# CORE.net
KiCad netlist of a schematic drawn in Altium Designer
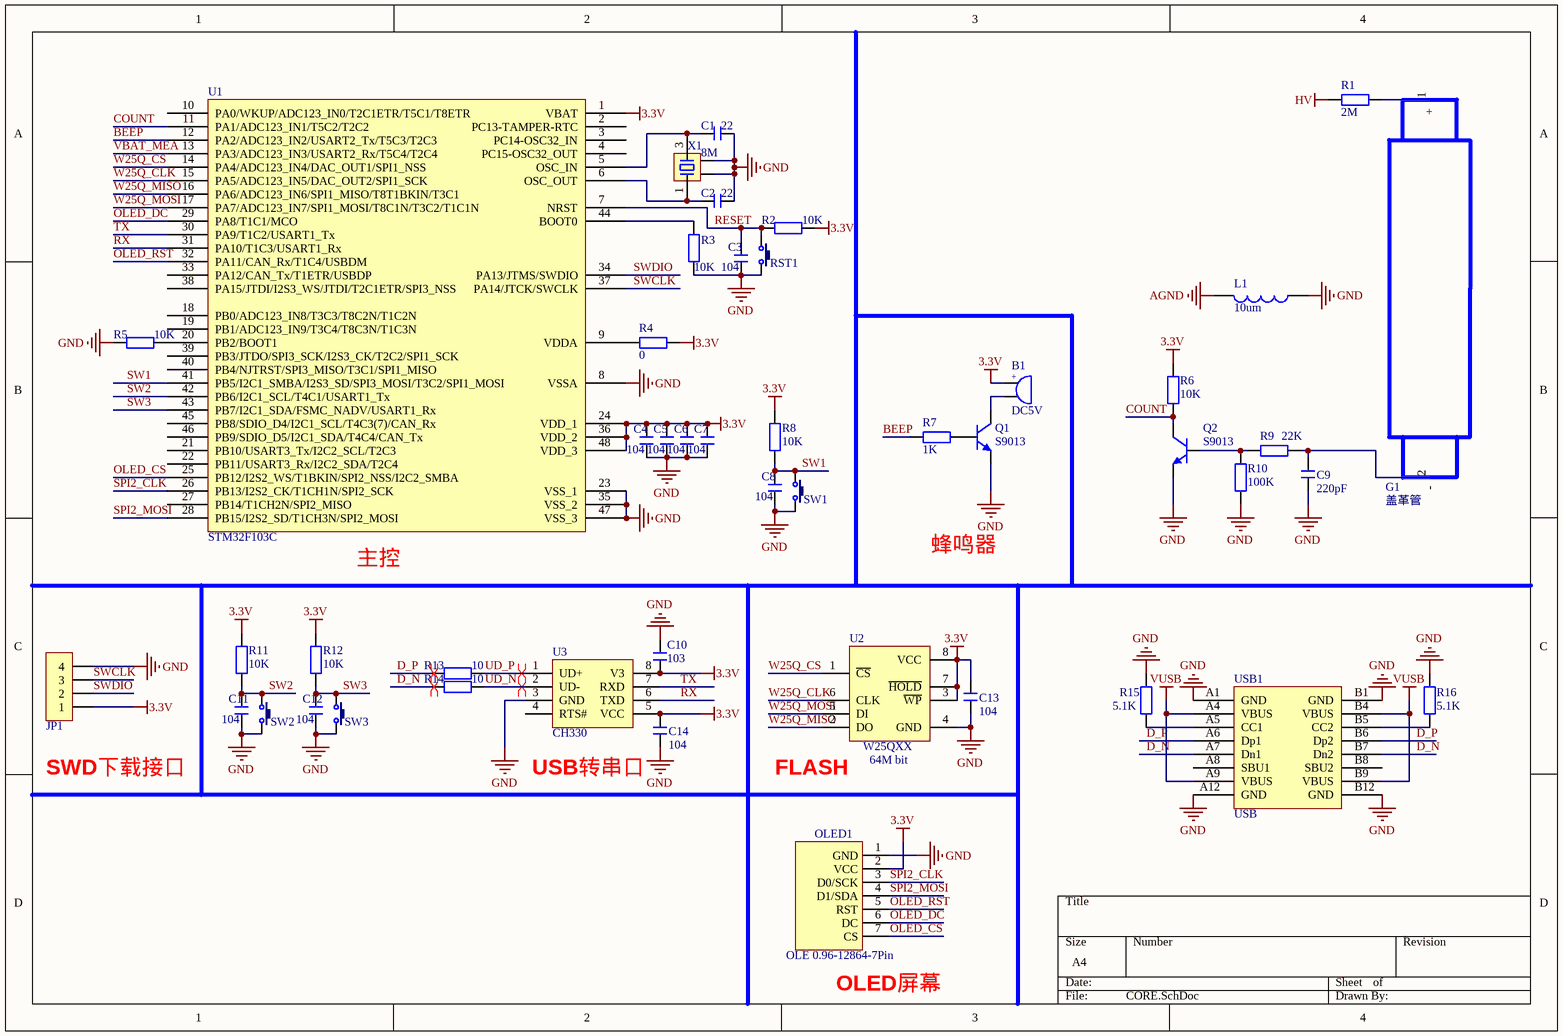
[diagram p0: CORE.SchDoc]

(export (version "E")
  (design (tool "Eeschema 10.0.6"))
  (components
    (comp (ref "B1")
      (value "DC5V")
      (footprint "BEEP 5x9x5.5")
      (description "蜂鸣器")
      (fields (field (name "版权归属") "源创客"))
      (libsource (lib "未分类器件") (part "BEEP"))
    )
    (comp (ref "C1")
      (value "22")
      (footprint "C 0603")
      (description "无极性贴片电容")
      (fields (field (name "版权归属") "源创客"))
      (libsource (lib "电阻-电容-电感") (part "C"))
    )
    (comp (ref "C2")
      (value "22")
      (footprint "C 0603")
      (description "无极性贴片电容")
      (fields (field (name "版权归属") "源创客"))
      (libsource (lib "电阻-电容-电感") (part "C"))
    )
    (comp (ref "C3")
      (value "104")
      (footprint "C 0603")
      (description "无极性贴片电容")
      (fields (field (name "版权归属") "源创客"))
      (libsource (lib "电阻-电容-电感") (part "C"))
    )
    (comp (ref "C4")
      (value "104")
      (footprint "C 0603")
      (description "无极性贴片电容")
      (fields (field (name "版权归属") "源创客"))
      (libsource (lib "电阻-电容-电感") (part "C"))
    )
    (comp (ref "C5")
      (value "104")
      (footprint "C 0603")
      (description "无极性贴片电容")
      (fields (field (name "版权归属") "源创客"))
      (libsource (lib "电阻-电容-电感") (part "C"))
    )
    (comp (ref "C6")
      (value "104")
      (footprint "C 0603")
      (description "无极性贴片电容")
      (fields (field (name "版权归属") "源创客"))
      (libsource (lib "电阻-电容-电感") (part "C"))
    )
    (comp (ref "C7")
      (value "104")
      (footprint "C 0603")
      (description "无极性贴片电容")
      (fields (field (name "版权归属") "源创客"))
      (libsource (lib "电阻-电容-电感") (part "C"))
    )
    (comp (ref "C8")
      (value "104")
      (footprint "C 0603")
      (description "无极性贴片电容")
      (fields (field (name "版权归属") "源创客"))
      (libsource (lib "电阻-电容-电感") (part "C"))
    )
    (comp (ref "C9")
      (value "220pF")
      (footprint "C 0603")
      (description "无极性贴片电容")
      (fields (field (name "版权归属") "源创客"))
      (libsource (lib "电阻-电容-电感") (part "C"))
    )
    (comp (ref "C10")
      (value "103")
      (footprint "C 0603")
      (description "无极性贴片电容")
      (fields (field (name "版权归属") "源创客"))
      (libsource (lib "电阻-电容-电感") (part "C"))
    )
    (comp (ref "C11")
      (value "104")
      (footprint "C 0603")
      (description "无极性贴片电容")
      (fields (field (name "版权归属") "源创客"))
      (libsource (lib "电阻-电容-电感") (part "C"))
    )
    (comp (ref "C12")
      (value "104")
      (footprint "C 0603")
      (description "无极性贴片电容")
      (fields (field (name "版权归属") "源创客"))
      (libsource (lib "电阻-电容-电感") (part "C"))
    )
    (comp (ref "C13")
      (value "104")
      (footprint "C 0603")
      (description "无极性贴片电容")
      (fields (field (name "版权归属") "源创客"))
      (libsource (lib "电阻-电容-电感") (part "C"))
    )
    (comp (ref "C14")
      (value "104")
      (footprint "C 0603")
      (description "无极性贴片电容")
      (fields (field (name "版权归属") "源创客"))
      (libsource (lib "电阻-电容-电感") (part "C"))
    )
    (comp (ref "G1")
      (value "盖革管")
      (footprint "SI3BG 2")
      (description "小型高量程SI3BG GM管")
      (libsource (lib "MYLIB") (part "盖革管"))
    )
    (comp (ref "JP1")
      (value "HDR-1X4")
      (footprint "SH1.0-4P-L")
      (description "4P接插件")
      (fields (field (name "版权归属") "源创客"))
      (libsource (lib "接插件") (part "Header 4"))
    )
    (comp (ref "L1")
      (value "10um")
      (footprint "L 0805")
      (description "小功率贴片电感")
      (fields (field (name "版权归属") "源创客"))
      (libsource (lib "电阻-电容-电感") (part "L"))
    )
    (comp (ref "OLED1")
      (value "OLE 0.96-12864-7Pin")
      (footprint "HDR-1X7_M")
      (libsource (lib "MyLibray") (part "OLE 0.96-12864-7Pin"))
    )
    (comp (ref "Q1")
      (value "S9013")
      (footprint "SOT23-3N")
      (description "低频放大-NPN型")
      (fields (field (name "版权归属") "源创客"))
      (libsource (lib "三极管") (part "9013-SMD"))
    )
    (comp (ref "Q2")
      (value "S9013")
      (footprint "SOT23-3N")
      (description "低频放大-NPN型")
      (fields (field (name "版权归属") "源创客"))
      (libsource (lib "三极管") (part "9013-SMD"))
    )
    (comp (ref "R1")
      (value "2M")
      (footprint "R 0603")
      (description "贴片电阻")
      (fields (field (name "版权归属") "源创客"))
      (libsource (lib "电阻-电容-电感") (part "R"))
    )
    (comp (ref "R2")
      (value "10K")
      (footprint "R 0603")
      (description "贴片电阻")
      (fields (field (name "版权归属") "源创客"))
      (libsource (lib "电阻-电容-电感") (part "R"))
    )
    (comp (ref "R3")
      (value "10K")
      (footprint "R 0603")
      (description "贴片电阻")
      (fields (field (name "版权归属") "源创客"))
      (libsource (lib "电阻-电容-电感") (part "R"))
    )
    (comp (ref "R4")
      (value "0")
      (footprint "R 0603")
      (description "贴片电阻")
      (fields (field (name "版权归属") "源创客"))
      (libsource (lib "电阻-电容-电感") (part "R"))
    )
    (comp (ref "R5")
      (value "10K")
      (footprint "R 0603")
      (description "贴片电阻")
      (fields (field (name "版权归属") "源创客"))
      (libsource (lib "电阻-电容-电感") (part "R"))
    )
    (comp (ref "R6")
      (value "10K")
      (footprint "R 0603")
      (description "贴片电阻")
      (fields (field (name "版权归属") "源创客"))
      (libsource (lib "电阻-电容-电感") (part "R"))
    )
    (comp (ref "R7")
      (value "1K")
      (footprint "R 0603")
      (description "贴片电阻")
      (fields (field (name "版权归属") "源创客"))
      (libsource (lib "电阻-电容-电感") (part "R"))
    )
    (comp (ref "R8")
      (value "10K")
      (footprint "R 0603")
      (description "贴片电阻")
      (fields (field (name "版权归属") "源创客"))
      (libsource (lib "电阻-电容-电感") (part "R"))
    )
    (comp (ref "R9")
      (value "22K")
      (footprint "R 0603")
      (description "贴片电阻")
      (fields (field (name "版权归属") "源创客"))
      (libsource (lib "电阻-电容-电感") (part "R"))
    )
    (comp (ref "R10")
      (value "100K")
      (footprint "R 0603")
      (description "贴片电阻")
      (fields (field (name "版权归属") "源创客"))
      (libsource (lib "电阻-电容-电感") (part "R"))
    )
    (comp (ref "R11")
      (value "10K")
      (footprint "R 0603")
      (description "贴片电阻")
      (fields (field (name "版权归属") "源创客"))
      (libsource (lib "电阻-电容-电感") (part "R"))
    )
    (comp (ref "R12")
      (value "10K")
      (footprint "R 0603")
      (description "贴片电阻")
      (fields (field (name "版权归属") "源创客"))
      (libsource (lib "电阻-电容-电感") (part "R"))
    )
    (comp (ref "R13")
      (value "10")
      (footprint "R 0603")
      (description "贴片电阻")
      (fields (field (name "版权归属") "源创客"))
      (libsource (lib "电阻-电容-电感") (part "R"))
    )
    (comp (ref "R14")
      (value "10")
      (footprint "R 0603")
      (description "贴片电阻")
      (fields (field (name "版权归属") "源创客"))
      (libsource (lib "电阻-电容-电感") (part "R"))
    )
    (comp (ref "R15")
      (value "5.1K")
      (footprint "R 0603")
      (description "贴片电阻")
      (fields (field (name "版权归属") "源创客"))
      (libsource (lib "电阻-电容-电感") (part "R"))
    )
    (comp (ref "R16")
      (value "5.1K")
      (footprint "R 0603")
      (description "贴片电阻")
      (fields (field (name "版权归属") "源创客"))
      (libsource (lib "电阻-电容-电感") (part "R"))
    )
    (comp (ref "RST1")
      (value "TSW")
      (footprint "TSW 2*4*3.5-S-W")
      (description "轻触开关")
      (fields (field (name "版权归属") "源创客"))
      (libsource (lib "按键-开关") (part "TSW SMD"))
    )
    (comp (ref "SW1")
      (value "TSW")
      (footprint "TSW 2*4*3.5-S-W")
      (description "轻触开关")
      (fields (field (name "版权归属") "源创客"))
      (libsource (lib "按键-开关") (part "TSW SMD"))
    )
    (comp (ref "SW2")
      (value "TSW")
      (footprint "TSW 2*4*3.5-S-W")
      (description "轻触开关")
      (fields (field (name "版权归属") "源创客"))
      (libsource (lib "按键-开关") (part "TSW SMD"))
    )
    (comp (ref "SW3")
      (value "TSW")
      (footprint "TSW 2*4*3.5-S-W")
      (description "轻触开关")
      (fields (field (name "版权归属") "源创客"))
      (libsource (lib "按键-开关") (part "TSW SMD"))
    )
    (comp (ref "U1")
      (value "STM32F103C")
      (footprint "LQFP-48_M")
      (description "STM32单片机48引脚")
      (libsource (lib "LIB") (part "STM32F103C"))
    )
    (comp (ref "U2")
      (value "W25QXX")
      (footprint "SOIC8_W")
      (description "SPI FLASH")
      (fields (field (name "MEMORY") "64M bit"))
      (libsource (lib "LIB") (part "W25QXX"))
    )
    (comp (ref "U3") (value "CH330") (footprint "SOIC8_N") (libsource (lib "LIB") (part "CH330")))
    (comp (ref "USB1")
      (value "USB")
      (footprint "USB-C/16P")
      (description "USB-C型母口16P/12P")
      (libsource (lib "接口类") (part "USB-C/16P"))
    )
    (comp (ref "X1")
      (value "8M")
      (footprint "XTAL-3225")
      (description "4脚晶振")
      (fields (field (name "版权归属") "源创客"))
      (libsource (lib "保险丝-晶振") (part "XTAL-4"))
    )
  )
  (nets
    (net (code "1") (name "/BEEP") (class "Default")
      (node (ref "R7") (pin "2") (pinfunction "2_2") (pintype "passive"))
      (node (ref "U1") (pin "12") (pinfunction "PA2/ADC123_IN2/USART2_Tx/T5C3/T2C3_12") (pintype "passive"))
    )
    (net (code "2") (name "/COUNT") (class "Default")
      (node (ref "Q2") (pin "3") (pinfunction "C_3") (pintype "passive"))
      (node (ref "R6") (pin "1") (pinfunction "1_1") (pintype "passive"))
      (node (ref "U1") (pin "11") (pinfunction "PA1/ADC123_IN1/T5C2/T2C2_11") (pintype "passive"))
    )
    (net (code "3") (name "/D_N") (class "Default")
      (node (ref "R14") (pin "1") (pinfunction "1_1") (pintype "passive"))
      (node (ref "USB1") (pin "A7") (pinfunction "Dn1_A7") (pintype "passive"))
      (node (ref "USB1") (pin "B7") (pinfunction "Dn2_B7") (pintype "passive"))
    )
    (net (code "4") (name "/D_P") (class "Default")
      (node (ref "R13") (pin "1") (pinfunction "1_1") (pintype "passive"))
      (node (ref "USB1") (pin "A6") (pinfunction "Dp1_A6") (pintype "passive"))
      (node (ref "USB1") (pin "B6") (pinfunction "Dp2_B6") (pintype "passive"))
    )
    (net (code "5") (name "/OLED_CS") (class "Default")
      (node (ref "OLED1") (pin "7") (pinfunction "CS_7") (pintype "passive"))
      (node (ref "U1") (pin "25") (pinfunction "PB12/I2S2_WS/T1BKIN/SPI2_NSS/I2C2_SMBA_25") (pintype "passive"))
    )
    (net (code "6") (name "/OLED_DC") (class "Default")
      (node (ref "OLED1") (pin "6") (pinfunction "DC_6") (pintype "passive"))
      (node (ref "U1") (pin "29") (pinfunction "PA8/T1C1/MCO_29") (pintype "passive"))
    )
    (net (code "7") (name "/OLED_RST") (class "Default")
      (node (ref "OLED1") (pin "5") (pinfunction "RST_5") (pintype "passive"))
      (node (ref "U1") (pin "32") (pinfunction "PA11/CAN_Rx/T1C4/USBDM_32") (pintype "passive"))
    )
    (net (code "8") (name "/RESET") (class "Default")
      (node (ref "C3") (pin "2") (pinfunction "2_2") (pintype "passive"))
      (node (ref "R2") (pin "2") (pinfunction "2_2") (pintype "passive"))
      (node (ref "RST1") (pin "2") (pinfunction "2_2") (pintype "passive"))
      (node (ref "U1") (pin "7") (pinfunction "NRST_7") (pintype "passive"))
    )
    (net (code "9") (name "/RX") (class "Default")
      (node (ref "U1") (pin "31") (pinfunction "PA10/T1C3/USART1_Rx_31") (pintype "passive"))
      (node (ref "U3") (pin "6") (pinfunction "TXD_6") (pintype "passive"))
    )
    (net (code "10") (name "/SPI2_CLK") (class "Default")
      (node (ref "OLED1") (pin "3") (pinfunction "D0/SCK_3") (pintype "passive"))
      (node (ref "U1") (pin "26") (pinfunction "PB13/I2S2_CK/T1CH1N/SPI2_SCK_26") (pintype "passive"))
    )
    (net (code "11") (name "/SPI2_MOSI") (class "Default")
      (node (ref "OLED1") (pin "4") (pinfunction "D1/SDA_4") (pintype "passive"))
      (node (ref "U1") (pin "28") (pinfunction "PB15/I2S2_SD/T1CH3N/SPI2_MOSI_28") (pintype "passive"))
    )
    (net (code "12") (name "/SW1") (class "Default")
      (node (ref "C8") (pin "2") (pinfunction "2_2") (pintype "passive"))
      (node (ref "R8") (pin "2") (pinfunction "2_2") (pintype "passive"))
      (node (ref "SW1") (pin "2") (pinfunction "2_2") (pintype "passive"))
      (node (ref "U1") (pin "41") (pinfunction "PB5/I2C1_SMBA/I2S3_SD/SPI3_MOSI/T3C2/SPI1_MOSI_41") (pintype "passive"))
    )
    (net (code "13") (name "/SW2") (class "Default")
      (node (ref "C11") (pin "2") (pinfunction "2_2") (pintype "passive"))
      (node (ref "R11") (pin "2") (pinfunction "2_2") (pintype "passive"))
      (node (ref "SW2") (pin "2") (pinfunction "2_2") (pintype "passive"))
      (node (ref "U1") (pin "42") (pinfunction "PB6/I2C1_SCL/T4C1/USART1_Tx_42") (pintype "passive"))
    )
    (net (code "14") (name "/SW3") (class "Default")
      (node (ref "C12") (pin "2") (pinfunction "2_2") (pintype "passive"))
      (node (ref "R12") (pin "2") (pinfunction "2_2") (pintype "passive"))
      (node (ref "SW3") (pin "2") (pinfunction "2_2") (pintype "passive"))
      (node (ref "U1") (pin "43") (pinfunction "PB7/I2C1_SDA/FSMC_NADV/USART1_Rx_43") (pintype "passive"))
    )
    (net (code "15") (name "/SWCLK") (class "Default")
      (node (ref "JP1") (pin "3") (pinfunction "3_3") (pintype "passive"))
      (node (ref "U1") (pin "37") (pinfunction "PA14/JTCK/SWCLK_37") (pintype "passive"))
    )
    (net (code "16") (name "/SWDIO") (class "Default")
      (node (ref "JP1") (pin "2") (pinfunction "2_2") (pintype "passive"))
      (node (ref "U1") (pin "34") (pinfunction "PA13/JTMS/SWDIO_34") (pintype "passive"))
    )
    (net (code "17") (name "/TX") (class "Default")
      (node (ref "U1") (pin "30") (pinfunction "PA9/T1C2/USART1_Tx_30") (pintype "passive"))
      (node (ref "U3") (pin "7") (pinfunction "RXD_7") (pintype "passive"))
    )
    (net (code "18") (name "/UD_N") (class "Default")
      (node (ref "R14") (pin "2") (pinfunction "2_2") (pintype "passive"))
      (node (ref "U3") (pin "2") (pinfunction "UD-_2") (pintype "passive"))
    )
    (net (code "19") (name "/UD_P") (class "Default")
      (node (ref "R13") (pin "2") (pinfunction "2_2") (pintype "passive"))
      (node (ref "U3") (pin "1") (pinfunction "UD+_1") (pintype "passive"))
    )
    (net (code "20") (name "/VBAT_MEA") (class "Default")
      (node (ref "U1") (pin "13") (pinfunction "PA3/ADC123_IN3/USART2_Rx/T5C4/T2C4_13") (pintype "passive"))
    )
    (net (code "21") (name "/W25Q_CLK") (class "Default")
      (node (ref "U1") (pin "15") (pinfunction "PA5/ADC123_IN5/DAC_OUT2/SPI1_SCK_15") (pintype "passive"))
      (node (ref "U2") (pin "6") (pinfunction "CLK_6") (pintype "passive"))
    )
    (net (code "22") (name "/W25Q_CS") (class "Default")
      (node (ref "U1") (pin "14") (pinfunction "PA4/ADC123_IN4/DAC_OUT1/SPI1_NSS_14") (pintype "passive"))
      (node (ref "U2") (pin "1") (pinfunction "~{CS}_1") (pintype "passive"))
    )
    (net (code "23") (name "/W25Q_MISO") (class "Default")
      (node (ref "U1") (pin "16") (pinfunction "PA6/ADC123_IN6/SPI1_MISO/T8T1BKIN/T3C1_16") (pintype "passive"))
      (node (ref "U2") (pin "2") (pinfunction "DO_2") (pintype "passive"))
    )
    (net (code "24") (name "/W25Q_MOSI") (class "Default")
      (node (ref "U1") (pin "17") (pinfunction "PA7/ADC123_IN7/SPI1_MOSI/T8C1N/T3C2/T1C1N_17") (pintype "passive"))
      (node (ref "U2") (pin "5") (pinfunction "DI_5") (pintype "passive"))
    )
    (net (code "25") (name "3.3V") (class "Default")
      (node (ref "B1") (pin "1") (pinfunction "1_1") (pintype "passive"))
      (node (ref "C10") (pin "1") (pinfunction "1_1") (pintype "passive"))
      (node (ref "C13") (pin "2") (pinfunction "2_2") (pintype "passive"))
      (node (ref "C14") (pin "2") (pinfunction "2_2") (pintype "passive"))
      (node (ref "C4") (pin "2") (pinfunction "2_2") (pintype "passive"))
      (node (ref "C5") (pin "2") (pinfunction "2_2") (pintype "passive"))
      (node (ref "C6") (pin "2") (pinfunction "2_2") (pintype "passive"))
      (node (ref "C7") (pin "2") (pinfunction "2_2") (pintype "passive"))
      (node (ref "JP1") (pin "1") (pinfunction "1_1") (pintype "passive"))
      (node (ref "OLED1") (pin "2") (pinfunction "VCC_2") (pintype "passive"))
      (node (ref "R11") (pin "1") (pinfunction "1_1") (pintype "passive"))
      (node (ref "R12") (pin "1") (pinfunction "1_1") (pintype "passive"))
      (node (ref "R2") (pin "1") (pinfunction "1_1") (pintype "passive"))
      (node (ref "R4") (pin "1") (pinfunction "1_1") (pintype "passive"))
      (node (ref "R6") (pin "2") (pinfunction "2_2") (pintype "passive"))
      (node (ref "R8") (pin "1") (pinfunction "1_1") (pintype "passive"))
      (node (ref "U1") (pin "1") (pinfunction "VBAT_1") (pintype "passive"))
      (node (ref "U1") (pin "24") (pinfunction "VDD_1_24") (pintype "passive"))
      (node (ref "U1") (pin "36") (pinfunction "VDD_2_36") (pintype "passive"))
      (node (ref "U1") (pin "48") (pinfunction "VDD_3_48") (pintype "passive"))
      (node (ref "U2") (pin "3") (pinfunction "~{WP}_3") (pintype "passive"))
      (node (ref "U2") (pin "7") (pinfunction "~{HOLD}_7") (pintype "passive"))
      (node (ref "U2") (pin "8") (pinfunction "VCC_8") (pintype "passive"))
      (node (ref "U3") (pin "5") (pinfunction "VCC_5") (pintype "passive"))
      (node (ref "U3") (pin "8") (pinfunction "V3_8") (pintype "passive"))
    )
    (net (code "26") (name "AGND") (class "Default")
      (node (ref "L1") (pin "2") (pinfunction "2_2") (pintype "passive"))
    )
    (net (code "27") (name "GND") (class "Default")
      (node (ref "C1") (pin "2") (pinfunction "2_2") (pintype "passive"))
      (node (ref "C10") (pin "2") (pinfunction "2_2") (pintype "passive"))
      (node (ref "C11") (pin "1") (pinfunction "1_1") (pintype "passive"))
      (node (ref "C12") (pin "1") (pinfunction "1_1") (pintype "passive"))
      (node (ref "C13") (pin "1") (pinfunction "1_1") (pintype "passive"))
      (node (ref "C14") (pin "1") (pinfunction "1_1") (pintype "passive"))
      (node (ref "C2") (pin "2") (pinfunction "2_2") (pintype "passive"))
      (node (ref "C3") (pin "1") (pinfunction "1_1") (pintype "passive"))
      (node (ref "C4") (pin "1") (pinfunction "1_1") (pintype "passive"))
      (node (ref "C5") (pin "1") (pinfunction "1_1") (pintype "passive"))
      (node (ref "C6") (pin "1") (pinfunction "1_1") (pintype "passive"))
      (node (ref "C7") (pin "1") (pinfunction "1_1") (pintype "passive"))
      (node (ref "C8") (pin "1") (pinfunction "1_1") (pintype "passive"))
      (node (ref "C9") (pin "1") (pinfunction "1_1") (pintype "passive"))
      (node (ref "JP1") (pin "4") (pinfunction "4_4") (pintype "passive"))
      (node (ref "L1") (pin "1") (pinfunction "1_1") (pintype "passive"))
      (node (ref "OLED1") (pin "1") (pinfunction "GND_1") (pintype "passive"))
      (node (ref "Q1") (pin "2") (pinfunction "E_2") (pintype "passive"))
      (node (ref "Q2") (pin "2") (pinfunction "E_2") (pintype "passive"))
      (node (ref "R10") (pin "1") (pinfunction "1_1") (pintype "passive"))
      (node (ref "R15") (pin "2") (pinfunction "2_2") (pintype "passive"))
      (node (ref "R16") (pin "2") (pinfunction "2_2") (pintype "passive"))
      (node (ref "R3") (pin "1") (pinfunction "1_1") (pintype "passive"))
      (node (ref "R5") (pin "2") (pinfunction "2_2") (pintype "passive"))
      (node (ref "RST1") (pin "1") (pinfunction "1_1") (pintype "passive"))
      (node (ref "SW1") (pin "1") (pinfunction "1_1") (pintype "passive"))
      (node (ref "SW2") (pin "1") (pinfunction "1_1") (pintype "passive"))
      (node (ref "SW3") (pin "1") (pinfunction "1_1") (pintype "passive"))
      (node (ref "U1") (pin "23") (pinfunction "VSS_1_23") (pintype "passive"))
      (node (ref "U1") (pin "35") (pinfunction "VSS_2_35") (pintype "passive"))
      (node (ref "U1") (pin "47") (pinfunction "VSS_3_47") (pintype "passive"))
      (node (ref "U1") (pin "8") (pinfunction "VSSA_8") (pintype "passive"))
      (node (ref "U2") (pin "4") (pinfunction "GND_4") (pintype "passive"))
      (node (ref "U3") (pin "3") (pinfunction "GND_3") (pintype "passive"))
      (node (ref "USB1") (pin "A1") (pinfunction "GND_A1") (pintype "passive"))
      (node (ref "USB1") (pin "A12") (pinfunction "GND_A12") (pintype "passive"))
      (node (ref "USB1") (pin "B1") (pinfunction "GND_B1") (pintype "passive"))
      (node (ref "USB1") (pin "B12") (pinfunction "GND_B12") (pintype "passive"))
      (node (ref "X1") (pin "2") (pinfunction "2_2") (pintype "passive"))
      (node (ref "X1") (pin "4") (pinfunction "4_4") (pintype "passive"))
    )
    (net (code "28") (name "HV") (class "Default")
      (node (ref "R1") (pin "1") (pinfunction "1_1") (pintype "passive"))
    )
    (net (code "29") (name "Net-(G1-+)") (class "Default")
      (node (ref "G1") (pin "1") (pinfunction "+_1") (pintype "passive"))
      (node (ref "R1") (pin "2") (pinfunction "2_2") (pintype "passive"))
    )
    (net (code "30") (name "Net-(G1--)") (class "Default")
      (node (ref "C9") (pin "2") (pinfunction "2_2") (pintype "passive"))
      (node (ref "G1") (pin "2") (pinfunction "-_2") (pintype "passive"))
      (node (ref "R9") (pin "1") (pinfunction "1_1") (pintype "passive"))
    )
    (net (code "31") (name "Net-(Q1-B)") (class "Default")
      (node (ref "Q1") (pin "1") (pinfunction "B_1") (pintype "passive"))
      (node (ref "R7") (pin "1") (pinfunction "1_1") (pintype "passive"))
    )
    (net (code "32") (name "Net-(Q1-C)") (class "Default")
      (node (ref "B1") (pin "2") (pinfunction "2_2") (pintype "passive"))
      (node (ref "Q1") (pin "3") (pinfunction "C_3") (pintype "passive"))
    )
    (net (code "33") (name "Net-(Q2-B)") (class "Default")
      (node (ref "Q2") (pin "1") (pinfunction "B_1") (pintype "passive"))
      (node (ref "R10") (pin "2") (pinfunction "2_2") (pintype "passive"))
      (node (ref "R9") (pin "2") (pinfunction "2_2") (pintype "passive"))
    )
    (net (code "34") (name "Net-(U1-BOOT0)") (class "Default")
      (node (ref "R3") (pin "2") (pinfunction "2_2") (pintype "passive"))
      (node (ref "U1") (pin "44") (pinfunction "BOOT0_44") (pintype "passive"))
    )
    (net (code "35") (name "Net-(U1-OSC_IN)") (class "Default")
      (node (ref "C1") (pin "1") (pinfunction "1_1") (pintype "passive"))
      (node (ref "U1") (pin "5") (pinfunction "OSC_IN_5") (pintype "passive"))
      (node (ref "X1") (pin "3") (pinfunction "3_3") (pintype "passive"))
    )
    (net (code "36") (name "Net-(U1-OSC_OUT)") (class "Default")
      (node (ref "C2") (pin "1") (pinfunction "1_1") (pintype "passive"))
      (node (ref "U1") (pin "6") (pinfunction "OSC_OUT_6") (pintype "passive"))
      (node (ref "X1") (pin "1") (pinfunction "1_1") (pintype "passive"))
    )
    (net (code "37") (name "Net-(U1-PB2{slash}BOOT1)") (class "Default")
      (node (ref "R5") (pin "1") (pinfunction "1_1") (pintype "passive"))
      (node (ref "U1") (pin "20") (pinfunction "PB2/BOOT1_20") (pintype "passive"))
    )
    (net (code "38") (name "Net-(U1-VDDA)") (class "Default")
      (node (ref "R4") (pin "2") (pinfunction "2_2") (pintype "passive"))
      (node (ref "U1") (pin "9") (pinfunction "VDDA_9") (pintype "passive"))
    )
    (net (code "39") (name "Net-(USB1-CC1)") (class "Default")
      (node (ref "R15") (pin "1") (pinfunction "1_1") (pintype "passive"))
      (node (ref "USB1") (pin "A5") (pinfunction "CC1_A5") (pintype "passive"))
    )
    (net (code "40") (name "Net-(USB1-CC2)") (class "Default")
      (node (ref "R16") (pin "1") (pinfunction "1_1") (pintype "passive"))
      (node (ref "USB1") (pin "B5") (pinfunction "CC2_B5") (pintype "passive"))
    )
    (net (code "41") (name "VUSB") (class "Default")
      (node (ref "USB1") (pin "A4") (pinfunction "VBUS_A4") (pintype "passive"))
      (node (ref "USB1") (pin "A9") (pinfunction "VBUS_A9") (pintype "passive"))
      (node (ref "USB1") (pin "B4") (pinfunction "VBUS_B4") (pintype "passive"))
      (node (ref "USB1") (pin "B9") (pinfunction "VBUS_B9") (pintype "passive"))
    )
    (net (code "42") (name "unconnected-(U1-PA0{slash}WKUP{slash}ADC123_IN0{slash}T2C1ETR{slash}T5C1{slash}T8ETR-Pad10)") (class "Default")
      (node (ref "U1") (pin "10") (pinfunction "PA0/WKUP/ADC123_IN0/T2C1ETR/T5C1/T8ETR_10") (pintype "passive"))
    )
    (net (code "43") (name "unconnected-(U1-PA12{slash}CAN_Tx{slash}T1ETR{slash}USBDP-Pad33)") (class "Default")
      (node (ref "U1") (pin "33") (pinfunction "PA12/CAN_Tx/T1ETR/USBDP_33") (pintype "passive"))
    )
    (net (code "44") (name "unconnected-(U1-PA15{slash}JTDI{slash}I2S3_WS{slash}JTDI{slash}T2C1ETR{slash}SPI3_NSS-Pad38)") (class "Default")
      (node (ref "U1") (pin "38") (pinfunction "PA15/JTDI/I2S3_WS/JTDI/T2C1ETR/SPI3_NSS_38") (pintype "passive"))
    )
    (net (code "45") (name "unconnected-(U1-PB0{slash}ADC123_IN8{slash}T3C3{slash}T8C2N{slash}T1C2N-Pad18)") (class "Default")
      (node (ref "U1") (pin "18") (pinfunction "PB0/ADC123_IN8/T3C3/T8C2N/T1C2N_18") (pintype "passive"))
    )
    (net (code "46") (name "unconnected-(U1-PB1{slash}ADC123_IN9{slash}T3C4{slash}T8C3N{slash}T1C3N-Pad19)") (class "Default")
      (node (ref "U1") (pin "19") (pinfunction "PB1/ADC123_IN9/T3C4/T8C3N/T1C3N_19") (pintype "passive"))
    )
    (net (code "47") (name "unconnected-(U1-PB3{slash}JTDO{slash}SPI3_SCK{slash}I2S3_CK{slash}T2C2{slash}SPI1_SCK-Pad39)") (class "Default")
      (node (ref "U1") (pin "39") (pinfunction "PB3/JTDO/SPI3_SCK/I2S3_CK/T2C2/SPI1_SCK_39") (pintype "passive"))
    )
    (net (code "48") (name "unconnected-(U1-PB4{slash}NJTRST{slash}SPI3_MISO{slash}T3C1{slash}SPI1_MISO-Pad40)") (class "Default")
      (node (ref "U1") (pin "40") (pinfunction "PB4/NJTRST/SPI3_MISO/T3C1/SPI1_MISO_40") (pintype "passive"))
    )
    (net (code "49") (name "unconnected-(U1-PB8{slash}SDIO_D4{slash}I2C1_SCL{slash}T4C3(7){slash}CAN_Rx-Pad45)") (class "Default")
      (node (ref "U1") (pin "45") (pinfunction "PB8/SDIO_D4/I2C1_SCL/T4C3(7)/CAN_Rx_45") (pintype "passive"))
    )
    (net (code "50") (name "unconnected-(U1-PB9{slash}SDIO_D5{slash}I2C1_SDA{slash}T4C4{slash}CAN_Tx-Pad46)") (class "Default")
      (node (ref "U1") (pin "46") (pinfunction "PB9/SDIO_D5/I2C1_SDA/T4C4/CAN_Tx_46") (pintype "passive"))
    )
    (net (code "51") (name "unconnected-(U1-PB10{slash}USART3_Tx{slash}I2C2_SCL{slash}T2C3-Pad21)") (class "Default")
      (node (ref "U1") (pin "21") (pinfunction "PB10/USART3_Tx/I2C2_SCL/T2C3_21") (pintype "passive"))
    )
    (net (code "52") (name "unconnected-(U1-PB11{slash}USART3_Rx{slash}I2C2_SDA{slash}T2C4-Pad22)") (class "Default")
      (node (ref "U1") (pin "22") (pinfunction "PB11/USART3_Rx/I2C2_SDA/T2C4_22") (pintype "passive"))
    )
    (net (code "53") (name "unconnected-(U1-PB14{slash}T1CH2N{slash}SPI2_MISO-Pad27)") (class "Default")
      (node (ref "U1") (pin "27") (pinfunction "PB14/T1CH2N/SPI2_MISO_27") (pintype "passive"))
    )
    (net (code "54") (name "unconnected-(U1-PC13-TAMPER-RTC-Pad2)") (class "Default")
      (node (ref "U1") (pin "2") (pinfunction "PC13-TAMPER-RTC_2") (pintype "passive"))
    )
    (net (code "55") (name "unconnected-(U1-PC14-OSC32_IN-Pad3)") (class "Default")
      (node (ref "U1") (pin "3") (pinfunction "PC14-OSC32_IN_3") (pintype "passive"))
    )
    (net (code "56") (name "unconnected-(U1-PC15-OSC32_OUT-Pad4)") (class "Default")
      (node (ref "U1") (pin "4") (pinfunction "PC15-OSC32_OUT_4") (pintype "passive"))
    )
    (net (code "57") (name "unconnected-(U3-RTS#-Pad4)") (class "Default")
      (node (ref "U3") (pin "4") (pinfunction "RTS#_4") (pintype "passive"))
    )
    (net (code "58") (name "unconnected-(USB1-SBU1-PadA8)") (class "Default")
      (node (ref "USB1") (pin "A8") (pinfunction "SBU1_A8") (pintype "passive"))
    )
    (net (code "59") (name "unconnected-(USB1-SBU2-PadB8)") (class "Default")
      (node (ref "USB1") (pin "B8") (pinfunction "SBU2_B8") (pintype "passive"))
    )
  )
)
